# espr-temp.net
KiCad netlist of a schematic drawn in EAGLE
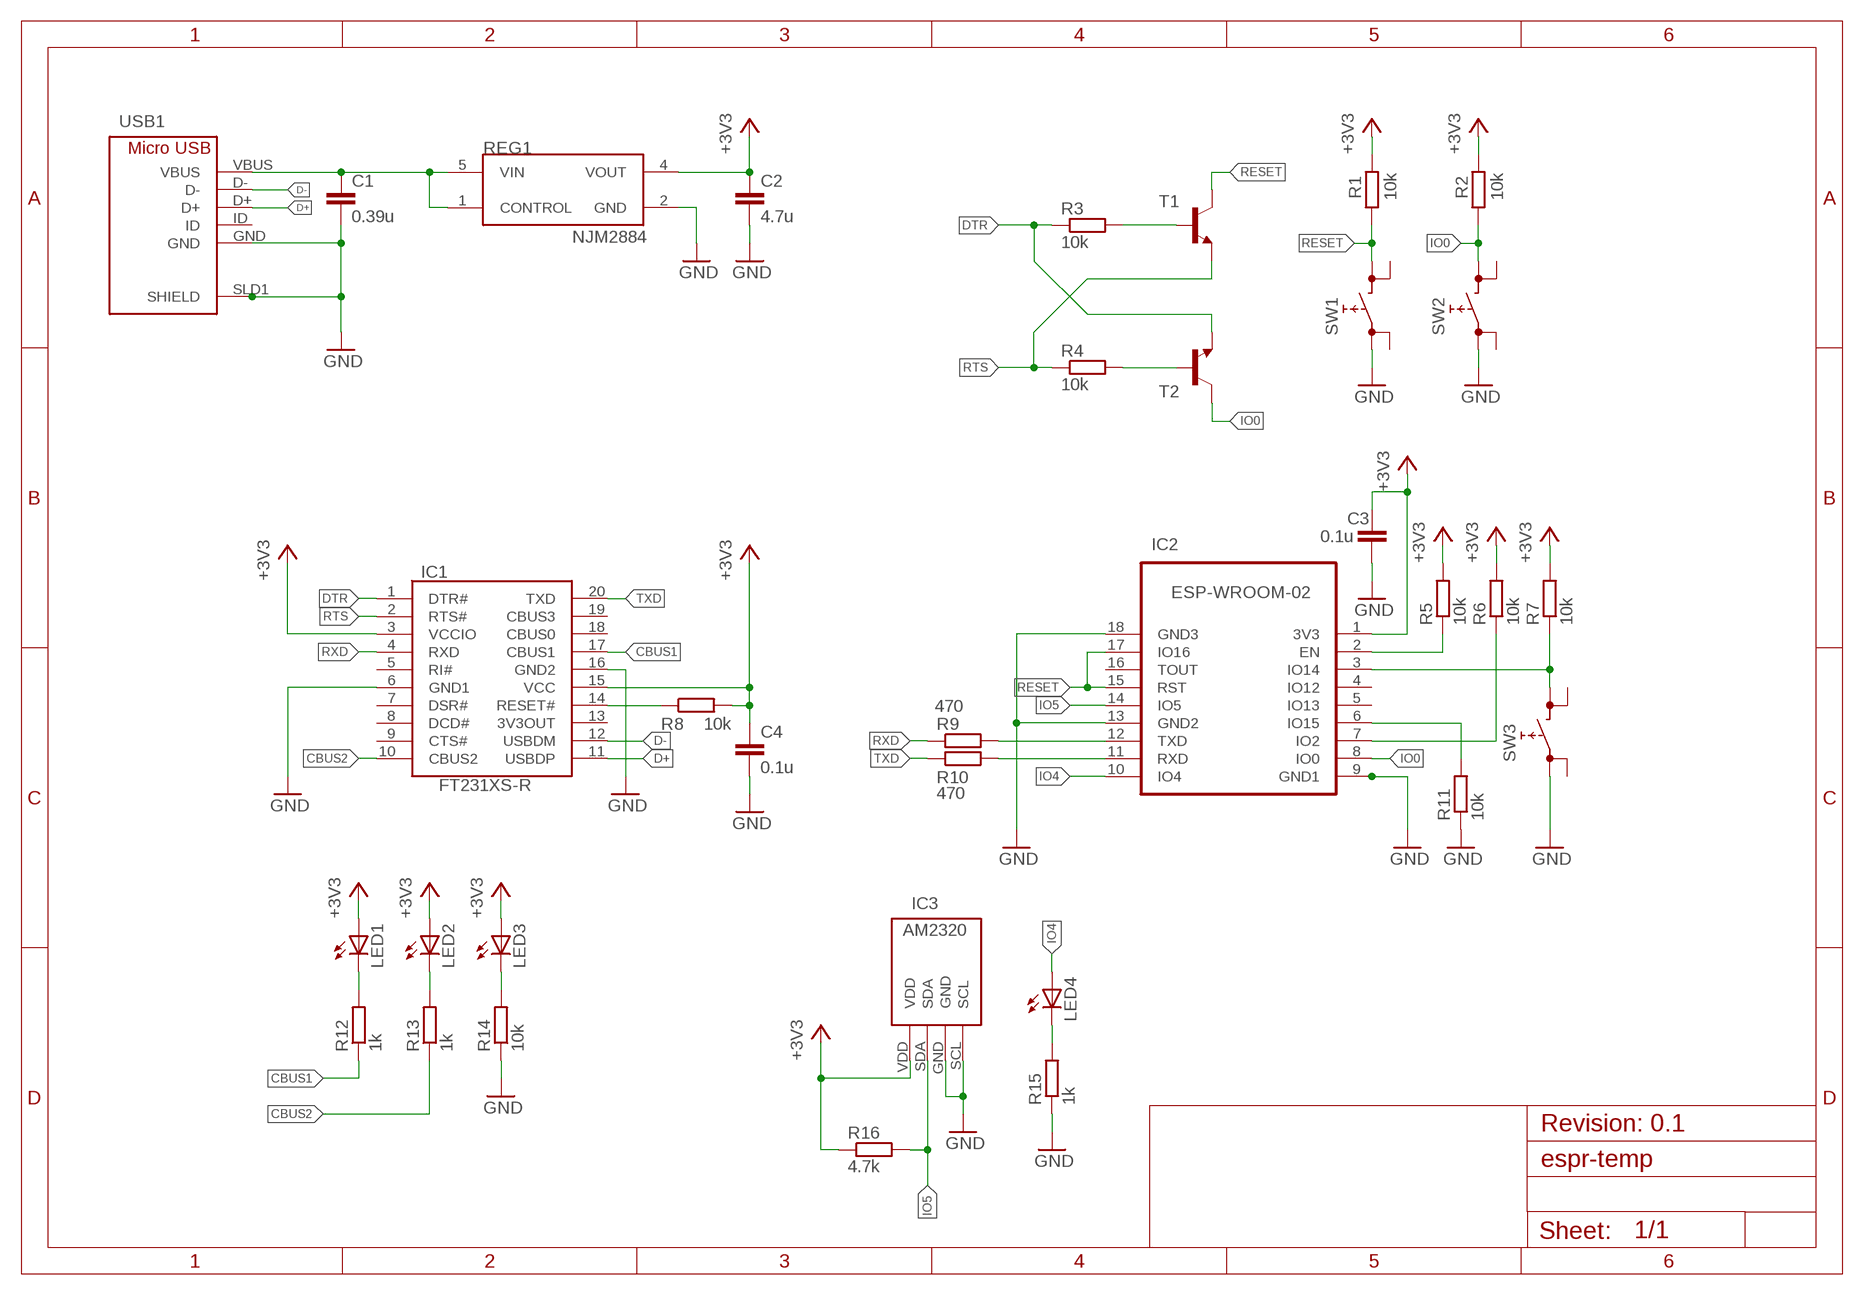
[diagram p0: schematic, sheet 1]

(export (version "E")
  (design (tool "Eeschema 10.0.6"))
  (components
    (comp (ref "C1")
      (value "0.39u")
      (footprint "eagle-import:C1608")
      (libsource (lib "eagle-import") (part "C-EUC1608"))
    )
    (comp (ref "C2")
      (value "4.7u")
      (footprint "eagle-import:C3216")
      (libsource (lib "eagle-import") (part "C-EUC3216"))
    )
    (comp (ref "C3")
      (value "0.1u")
      (footprint "eagle-import:C2012")
      (libsource (lib "eagle-import") (part "C-EUC2012"))
    )
    (comp (ref "C4")
      (value "0.1u")
      (footprint "eagle-import:C2012")
      (libsource (lib "eagle-import") (part "C-EUC2012"))
    )
    (comp (ref "IC1")
      (value "FT231XS-R")
      (footprint "eagle-import:SOP64P599X175-20N")
      (fields (field (name "RS_PART_NUMBER") "7570032P"))
      (libsource (lib "eagle-import") (part "FT231XS-R"))
    )
    (comp (ref "IC2")
      (value "ESP-WROOM-02")
      (footprint "eagle-import:ESP-WROOM-02")
      (libsource (lib "eagle-import") (part "ESP-WROOM-02"))
    )
    (comp (ref "IC3")
      (value "AM2320")
      (footprint "eagle-import:AM2320")
      (libsource (lib "eagle-import") (part "AM2320"))
    )
    (comp (ref "LED1")
      (value "OSHR1608")
      (footprint "eagle-import:C1608")
      (libsource (lib "eagle-import") (part "OSHR1608"))
    )
    (comp (ref "LED2")
      (value "OSYG1608")
      (footprint "eagle-import:C1608")
      (libsource (lib "eagle-import") (part "OSYG1608"))
    )
    (comp (ref "LED3")
      (value "OSYL1608")
      (footprint "eagle-import:C1608")
      (libsource (lib "eagle-import") (part "OSYL1608"))
    )
    (comp (ref "LED4")
      (value "OSBL1608")
      (footprint "eagle-import:C1608")
      (libsource (lib "eagle-import") (part "OSBL1608"))
    )
    (comp (ref "R1")
      (value "10k")
      (footprint "eagle-import:R1608")
      (libsource (lib "eagle-import") (part "R1608"))
    )
    (comp (ref "R2")
      (value "10k")
      (footprint "eagle-import:R1608")
      (libsource (lib "eagle-import") (part "R1608"))
    )
    (comp (ref "R3")
      (value "10k")
      (footprint "eagle-import:R1608")
      (libsource (lib "eagle-import") (part "R1608"))
    )
    (comp (ref "R4")
      (value "10k")
      (footprint "eagle-import:R1608")
      (libsource (lib "eagle-import") (part "R1608"))
    )
    (comp (ref "R5")
      (value "10k")
      (footprint "eagle-import:R1608")
      (libsource (lib "eagle-import") (part "R1608"))
    )
    (comp (ref "R6")
      (value "10k")
      (footprint "eagle-import:R1608")
      (libsource (lib "eagle-import") (part "R1608"))
    )
    (comp (ref "R7")
      (value "10k")
      (footprint "eagle-import:R1608")
      (libsource (lib "eagle-import") (part "R1608"))
    )
    (comp (ref "R8")
      (value "10k")
      (footprint "eagle-import:R1608")
      (libsource (lib "eagle-import") (part "R1608"))
    )
    (comp (ref "R9")
      (value "470")
      (footprint "eagle-import:R1608")
      (libsource (lib "eagle-import") (part "R1608"))
    )
    (comp (ref "R10")
      (value "470")
      (footprint "eagle-import:R1608")
      (libsource (lib "eagle-import") (part "R1608"))
    )
    (comp (ref "R11")
      (value "10k")
      (footprint "eagle-import:R1608")
      (libsource (lib "eagle-import") (part "R1608"))
    )
    (comp (ref "R12")
      (value "1k")
      (footprint "eagle-import:R1608")
      (libsource (lib "eagle-import") (part "R1608"))
    )
    (comp (ref "R13")
      (value "1k")
      (footprint "eagle-import:R1608")
      (libsource (lib "eagle-import") (part "R1608"))
    )
    (comp (ref "R14")
      (value "10k")
      (footprint "eagle-import:R1608")
      (libsource (lib "eagle-import") (part "R1608"))
    )
    (comp (ref "R15")
      (value "1k")
      (footprint "eagle-import:R1608")
      (libsource (lib "eagle-import") (part "R1608"))
    )
    (comp (ref "R16")
      (value "4.7k")
      (footprint "eagle-import:M0805")
      (libsource (lib "eagle-import") (part "R-EU_M0805"))
    )
    (comp (ref "REG1")
      (value "NJM2884")
      (footprint "eagle-import:NJM2884-SOT-89-5")
      (libsource (lib "eagle-import") (part "NJM2884"))
    )
    (comp (ref "SW1")
      (value "SKRPACE010")
      (footprint "eagle-import:SKRPACE010")
      (libsource (lib "eagle-import") (part "SKRPACE010"))
    )
    (comp (ref "SW2")
      (value "SKRPACE010")
      (footprint "eagle-import:SKRPACE010")
      (libsource (lib "eagle-import") (part "SKRPACE010"))
    )
    (comp (ref "SW3")
      (value "SKRPACE010")
      (footprint "eagle-import:SKRPACE010")
      (libsource (lib "eagle-import") (part "SKRPACE010"))
    )
    (comp (ref "T1")
      (value "2PD601A")
      (footprint "eagle-import:SOT346")
      (libsource (lib "eagle-import") (part "2PD601A"))
    )
    (comp (ref "T2")
      (value "2PD601A")
      (footprint "eagle-import:SOT346")
      (libsource (lib "eagle-import") (part "2PD601A"))
    )
    (comp (ref "USB1")
      (value "MICRO-USB")
      (footprint "eagle-import:ZX62B5PA")
      (libsource (lib "eagle-import") (part "MICRO-USB"))
    )
  )
  (nets
    (net (code "1") (name "+3V3") (class "Default")
      (node (ref "C2") (pin "1") (pinfunction "1_1") (pintype "passive"))
      (node (ref "C3") (pin "1") (pinfunction "1_1") (pintype "passive"))
      (node (ref "C4") (pin "1") (pinfunction "1_1") (pintype "passive"))
      (node (ref "IC1") (pin "15") (pinfunction "VCC_15") (pintype "power_in"))
      (node (ref "IC1") (pin "3") (pinfunction "VCCIO_3") (pintype "power_in"))
      (node (ref "IC2") (pin "1") (pinfunction "3V3_1") (pintype "power_in"))
      (node (ref "IC3") (pin "VDD") (pinfunction "VDD_VDD") (pintype "power_in"))
      (node (ref "LED1") (pin "A") (pinfunction "A_A") (pintype "passive"))
      (node (ref "LED2") (pin "A") (pinfunction "A_A") (pintype "passive"))
      (node (ref "LED3") (pin "A") (pinfunction "A_A") (pintype "passive"))
      (node (ref "R1") (pin "2") (pinfunction "2_2") (pintype "passive"))
      (node (ref "R16") (pin "1") (pinfunction "1_1") (pintype "passive"))
      (node (ref "R2") (pin "2") (pinfunction "2_2") (pintype "passive"))
      (node (ref "R5") (pin "2") (pinfunction "2_2") (pintype "passive"))
      (node (ref "R6") (pin "2") (pinfunction "2_2") (pintype "passive"))
      (node (ref "R7") (pin "2") (pinfunction "2_2") (pintype "passive"))
      (node (ref "R8") (pin "2") (pinfunction "2_2") (pintype "passive"))
      (node (ref "REG1") (pin "4") (pinfunction "VOUT_4") (pintype "power_in"))
    )
    (net (code "2") (name "CBUS1") (class "Default")
      (node (ref "IC1") (pin "17") (pinfunction "CBUS1_17") (pintype "bidirectional"))
      (node (ref "R12") (pin "1") (pinfunction "1_1") (pintype "passive"))
    )
    (net (code "3") (name "CBUS2") (class "Default")
      (node (ref "IC1") (pin "10") (pinfunction "CBUS2_10") (pintype "bidirectional"))
      (node (ref "R13") (pin "1") (pinfunction "1_1") (pintype "passive"))
    )
    (net (code "4") (name "D+") (class "Default")
      (node (ref "IC1") (pin "11") (pinfunction "USBDP_11") (pintype "bidirectional"))
      (node (ref "USB1") (pin "D+") (pinfunction "D+_D+") (pintype "bidirectional"))
    )
    (net (code "5") (name "D-") (class "Default")
      (node (ref "IC1") (pin "12") (pinfunction "USBDM_12") (pintype "bidirectional"))
      (node (ref "USB1") (pin "D-") (pinfunction "D-_D-") (pintype "bidirectional"))
    )
    (net (code "6") (name "DTR") (class "Default")
      (node (ref "IC1") (pin "1") (pinfunction "DTR#_1") (pintype "bidirectional"))
      (node (ref "R3") (pin "1") (pinfunction "1_1") (pintype "passive"))
      (node (ref "T2") (pin "2") (pinfunction "E_2") (pintype "passive"))
    )
    (net (code "7") (name "GND") (class "Default")
      (node (ref "C1") (pin "2") (pinfunction "2_2") (pintype "passive"))
      (node (ref "C2") (pin "2") (pinfunction "2_2") (pintype "passive"))
      (node (ref "C3") (pin "2") (pinfunction "2_2") (pintype "passive"))
      (node (ref "C4") (pin "2") (pinfunction "2_2") (pintype "passive"))
      (node (ref "IC1") (pin "16") (pinfunction "GND2_16") (pintype "power_in"))
      (node (ref "IC1") (pin "6") (pinfunction "GND1_6") (pintype "power_in"))
      (node (ref "IC2") (pin "13") (pinfunction "GND2_13") (pintype "power_in"))
      (node (ref "IC2") (pin "18") (pinfunction "GND3_18") (pintype "power_in"))
      (node (ref "IC2") (pin "19") (pinfunction "GND0_19") (pintype "power_in"))
      (node (ref "IC2") (pin "9") (pinfunction "GND1_9") (pintype "power_in"))
      (node (ref "IC3") (pin "GND") (pinfunction "GND_GND") (pintype "power_in"))
      (node (ref "IC3") (pin "SCL") (pinfunction "SCL_SCL") (pintype "bidirectional"))
      (node (ref "R11") (pin "1") (pinfunction "1_1") (pintype "passive"))
      (node (ref "R14") (pin "1") (pinfunction "1_1") (pintype "passive"))
      (node (ref "R15") (pin "1") (pinfunction "1_1") (pintype "passive"))
      (node (ref "REG1") (pin "2") (pinfunction "GND_2") (pintype "power_in"))
      (node (ref "SW1") (pin "1") (pinfunction "0_1") (pintype "passive"))
      (node (ref "SW2") (pin "1") (pinfunction "0_1") (pintype "passive"))
      (node (ref "SW3") (pin "1") (pinfunction "0_1") (pintype "passive"))
      (node (ref "USB1") (pin "GND") (pinfunction "GND_GND") (pintype "power_in"))
      (node (ref "USB1") (pin "SLD1") (pinfunction "SHIELD_SLD1") (pintype "bidirectional"))
      (node (ref "USB1") (pin "SLD2") (pinfunction "SHIELD2_SLD2") (pintype "bidirectional"))
      (node (ref "USB1") (pin "SLD3") (pinfunction "SHIELD3_SLD3") (pintype "bidirectional"))
      (node (ref "USB1") (pin "SLD4") (pinfunction "SHIELD4_SLD4") (pintype "bidirectional"))
      (node (ref "USB1") (pin "SLD5") (pinfunction "SHIELD5_SLD5") (pintype "bidirectional"))
      (node (ref "USB1") (pin "SLD6") (pinfunction "SHIELD6_SLD6") (pintype "bidirectional"))
    )
    (net (code "8") (name "IO0") (class "Default")
      (node (ref "IC2") (pin "8") (pinfunction "IO0_8") (pintype "bidirectional"))
      (node (ref "R2") (pin "1") (pinfunction "1_1") (pintype "passive"))
      (node (ref "SW2") (pin "3") (pinfunction "1_3") (pintype "passive"))
      (node (ref "T2") (pin "3") (pinfunction "C_3") (pintype "passive"))
    )
    (net (code "9") (name "IO4") (class "Default")
      (node (ref "IC2") (pin "10") (pinfunction "IO4_10") (pintype "bidirectional"))
      (node (ref "LED4") (pin "A") (pinfunction "A_A") (pintype "passive"))
    )
    (net (code "10") (name "IO5") (class "Default")
      (node (ref "IC2") (pin "14") (pinfunction "IO5_14") (pintype "open_collector"))
      (node (ref "IC3") (pin "SDA") (pinfunction "SDA_SDA") (pintype "bidirectional"))
      (node (ref "R16") (pin "2") (pinfunction "2_2") (pintype "passive"))
    )
    (net (code "11") (name "Net-(IC1-RESET#)") (class "Default")
      (node (ref "IC1") (pin "14") (pinfunction "RESET#_14") (pintype "bidirectional"))
      (node (ref "R8") (pin "1") (pinfunction "1_1") (pintype "passive"))
    )
    (net (code "12") (name "Net-(IC2-EN)") (class "Default")
      (node (ref "IC2") (pin "2") (pinfunction "EN_2") (pintype "bidirectional"))
      (node (ref "R5") (pin "1") (pinfunction "1_1") (pintype "passive"))
    )
    (net (code "13") (name "Net-(IC2-IO2)") (class "Default")
      (node (ref "IC2") (pin "7") (pinfunction "IO2_7") (pintype "bidirectional"))
      (node (ref "R6") (pin "1") (pinfunction "1_1") (pintype "passive"))
    )
    (net (code "14") (name "Net-(IC2-IO14)") (class "Default")
      (node (ref "IC2") (pin "3") (pinfunction "IO14_3") (pintype "bidirectional"))
      (node (ref "R7") (pin "1") (pinfunction "1_1") (pintype "passive"))
      (node (ref "SW3") (pin "3") (pinfunction "1_3") (pintype "passive"))
    )
    (net (code "15") (name "Net-(IC2-IO15)") (class "Default")
      (node (ref "IC2") (pin "6") (pinfunction "IO15_6") (pintype "bidirectional"))
      (node (ref "R11") (pin "2") (pinfunction "2_2") (pintype "passive"))
    )
    (net (code "16") (name "Net-(IC2-RXD)") (class "Default")
      (node (ref "IC2") (pin "11") (pinfunction "RXD_11") (pintype "bidirectional"))
      (node (ref "R10") (pin "2") (pinfunction "2_2") (pintype "passive"))
    )
    (net (code "17") (name "Net-(IC2-TXD)") (class "Default")
      (node (ref "IC2") (pin "12") (pinfunction "TXD_12") (pintype "bidirectional"))
      (node (ref "R9") (pin "2") (pinfunction "2_2") (pintype "passive"))
    )
    (net (code "18") (name "Net-(LED1-PadC)") (class "Default")
      (node (ref "LED1") (pin "C") (pinfunction "C_C") (pintype "passive"))
      (node (ref "R12") (pin "2") (pinfunction "2_2") (pintype "passive"))
    )
    (net (code "19") (name "Net-(LED2-PadC)") (class "Default")
      (node (ref "LED2") (pin "C") (pinfunction "C_C") (pintype "passive"))
      (node (ref "R13") (pin "2") (pinfunction "2_2") (pintype "passive"))
    )
    (net (code "20") (name "Net-(LED3-PadC)") (class "Default")
      (node (ref "LED3") (pin "C") (pinfunction "C_C") (pintype "passive"))
      (node (ref "R14") (pin "2") (pinfunction "2_2") (pintype "passive"))
    )
    (net (code "21") (name "Net-(LED4-PadC)") (class "Default")
      (node (ref "LED4") (pin "C") (pinfunction "C_C") (pintype "passive"))
      (node (ref "R15") (pin "2") (pinfunction "2_2") (pintype "passive"))
    )
    (net (code "22") (name "Net-(REG1-CONTROL)") (class "Default")
      (node (ref "C1") (pin "1") (pinfunction "1_1") (pintype "passive"))
      (node (ref "REG1") (pin "1") (pinfunction "CONTROL_1") (pintype "bidirectional"))
      (node (ref "REG1") (pin "5") (pinfunction "VIN_5") (pintype "power_in"))
      (node (ref "USB1") (pin "VBUS") (pinfunction "VBUS_VBUS") (pintype "power_in"))
    )
    (net (code "23") (name "Net-(T1-B)") (class "Default")
      (node (ref "R3") (pin "2") (pinfunction "2_2") (pintype "passive"))
      (node (ref "T1") (pin "1") (pinfunction "B_1") (pintype "passive"))
    )
    (net (code "24") (name "Net-(T2-B)") (class "Default")
      (node (ref "R4") (pin "2") (pinfunction "2_2") (pintype "passive"))
      (node (ref "T2") (pin "1") (pinfunction "B_1") (pintype "passive"))
    )
    (net (code "25") (name "RESET") (class "Default")
      (node (ref "IC2") (pin "15") (pinfunction "RST_15") (pintype "bidirectional"))
      (node (ref "IC2") (pin "17") (pinfunction "IO16_17") (pintype "bidirectional"))
      (node (ref "R1") (pin "1") (pinfunction "1_1") (pintype "passive"))
      (node (ref "SW1") (pin "3") (pinfunction "1_3") (pintype "passive"))
      (node (ref "T1") (pin "3") (pinfunction "C_3") (pintype "passive"))
    )
    (net (code "26") (name "RTS") (class "Default")
      (node (ref "IC1") (pin "2") (pinfunction "RTS#_2") (pintype "bidirectional"))
      (node (ref "R4") (pin "1") (pinfunction "1_1") (pintype "passive"))
      (node (ref "T1") (pin "2") (pinfunction "E_2") (pintype "passive"))
    )
    (net (code "27") (name "RXD") (class "Default")
      (node (ref "IC1") (pin "4") (pinfunction "RXD_4") (pintype "bidirectional"))
      (node (ref "R9") (pin "1") (pinfunction "1_1") (pintype "passive"))
    )
    (net (code "28") (name "TXD") (class "Default")
      (node (ref "IC1") (pin "20") (pinfunction "TXD_20") (pintype "bidirectional"))
      (node (ref "R10") (pin "1") (pinfunction "1_1") (pintype "passive"))
    )
    (net (code "29") (name "unconnected-(IC1-3V3OUT-Pad13)") (class "Default")
      (node (ref "IC1") (pin "13") (pinfunction "3V3OUT_13") (pintype "output"))
    )
    (net (code "30") (name "unconnected-(IC1-CBUS0-Pad18)") (class "Default")
      (node (ref "IC1") (pin "18") (pinfunction "CBUS0_18") (pintype "bidirectional"))
    )
    (net (code "31") (name "unconnected-(IC1-CBUS3-Pad19)") (class "Default")
      (node (ref "IC1") (pin "19") (pinfunction "CBUS3_19") (pintype "bidirectional"))
    )
    (net (code "32") (name "unconnected-(IC1-CTS#-Pad9)") (class "Default")
      (node (ref "IC1") (pin "9") (pinfunction "CTS#_9") (pintype "bidirectional"))
    )
    (net (code "33") (name "unconnected-(IC1-DCD#-Pad8)") (class "Default")
      (node (ref "IC1") (pin "8") (pinfunction "DCD#_8") (pintype "bidirectional"))
    )
    (net (code "34") (name "unconnected-(IC1-DSR#-Pad7)") (class "Default")
      (node (ref "IC1") (pin "7") (pinfunction "DSR#_7") (pintype "bidirectional"))
    )
    (net (code "35") (name "unconnected-(IC1-RI#-Pad5)") (class "Default")
      (node (ref "IC1") (pin "5") (pinfunction "RI#_5") (pintype "bidirectional"))
    )
    (net (code "36") (name "unconnected-(IC2-IO12-Pad4)") (class "Default")
      (node (ref "IC2") (pin "4") (pinfunction "IO12_4") (pintype "bidirectional"))
    )
    (net (code "37") (name "unconnected-(IC2-IO13-Pad5)") (class "Default")
      (node (ref "IC2") (pin "5") (pinfunction "IO13_5") (pintype "bidirectional"))
    )
    (net (code "38") (name "unconnected-(IC2-TOUT-Pad16)") (class "Default")
      (node (ref "IC2") (pin "16") (pinfunction "TOUT_16") (pintype "bidirectional"))
    )
    (net (code "39") (name "unconnected-(SW1-0-Pad2)") (class "Default")
      (node (ref "SW1") (pin "2") (pinfunction "0_2") (pintype "passive"))
    )
    (net (code "40") (name "unconnected-(SW1-1-Pad4)") (class "Default")
      (node (ref "SW1") (pin "4") (pinfunction "1_4") (pintype "passive"))
    )
    (net (code "41") (name "unconnected-(SW2-0-Pad2)") (class "Default")
      (node (ref "SW2") (pin "2") (pinfunction "0_2") (pintype "passive"))
    )
    (net (code "42") (name "unconnected-(SW2-1-Pad4)") (class "Default")
      (node (ref "SW2") (pin "4") (pinfunction "1_4") (pintype "passive"))
    )
    (net (code "43") (name "unconnected-(SW3-0-Pad2)") (class "Default")
      (node (ref "SW3") (pin "2") (pinfunction "0_2") (pintype "passive"))
    )
    (net (code "44") (name "unconnected-(SW3-1-Pad4)") (class "Default")
      (node (ref "SW3") (pin "4") (pinfunction "1_4") (pintype "passive"))
    )
    (net (code "45") (name "unconnected-(USB1-PadID)") (class "Default")
      (node (ref "USB1") (pin "ID") (pinfunction "ID_ID") (pintype "bidirectional"))
    )
  )
)
